# Solider.net
KiCad netlist of a schematic drawn in Altium Designer
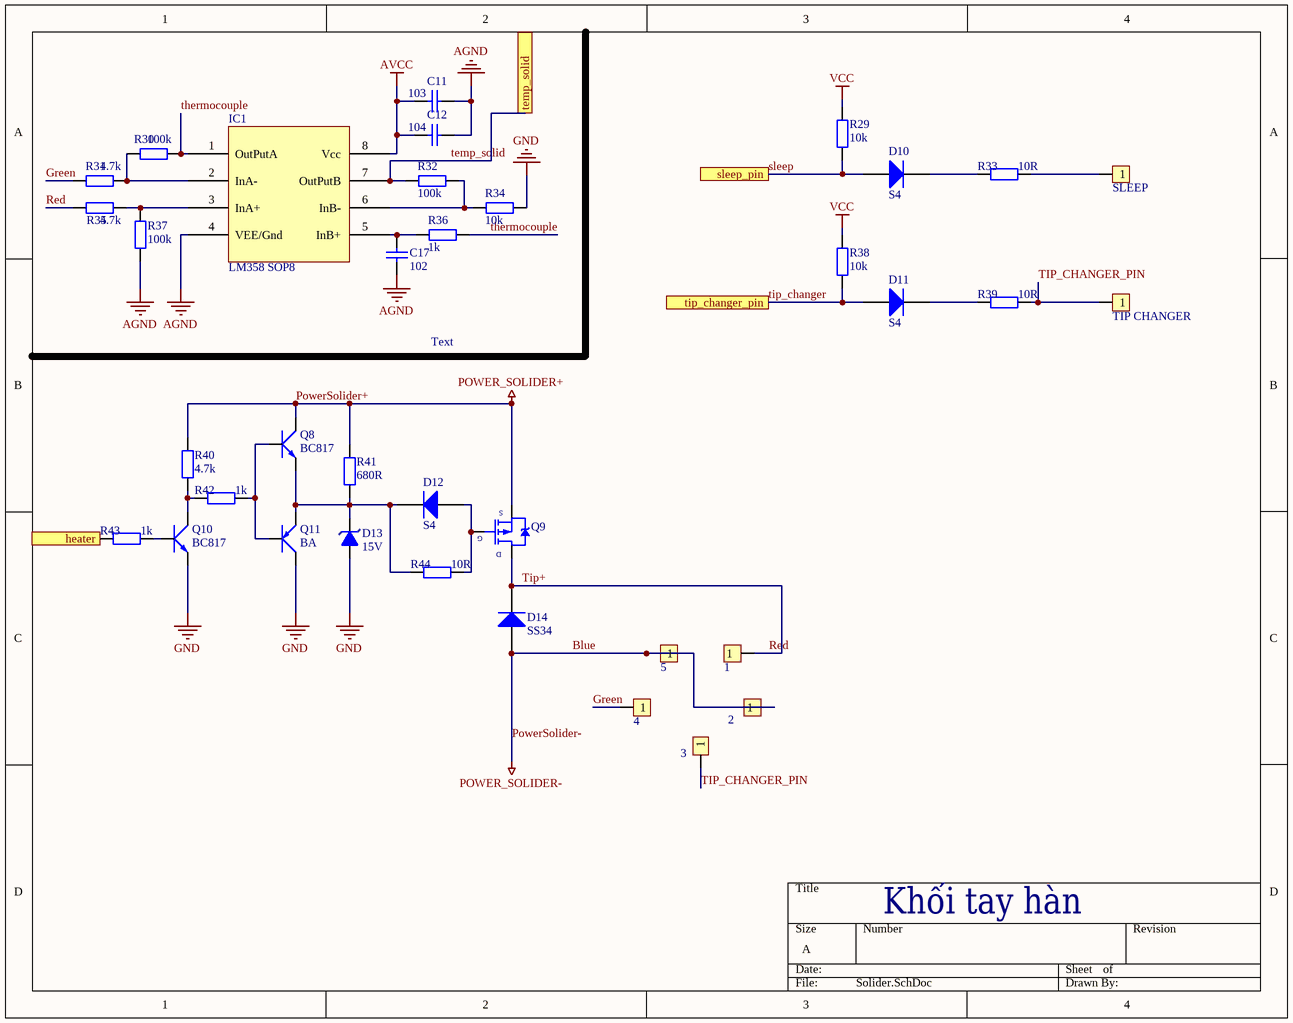
[diagram p0: Solider.SchDoc]

(export (version "E")
  (design (tool "Eeschema 10.0.6"))
  (components
    (comp (ref "C11")
      (value "103")
      (footprint "tu 0603")
      (description "Dán")
      (libsource (lib "Altium_Lib_by_KhueNguyenCreator") (part "Tu 0603 106 16V 20%"))
    )
    (comp (ref "C12")
      (value "104")
      (footprint "tu 0603")
      (description "Dán")
      (libsource (lib "Altium_Lib_by_KhueNguyenCreator") (part "Tu 0603 106 16V 20%"))
    )
    (comp (ref "C17")
      (value "102")
      (footprint "tu 0603")
      (description "Dán")
      (libsource (lib "Altium_Lib_by_KhueNguyenCreator") (part "Tu 0603 106 16V 20%"))
    )
    (comp (ref "D10")
      (value "S4")
      (footprint "DIODE SOD-123")
      (description "Dán")
      (libsource (lib "Driver4.0_Project_Fix_source_5V") (part "Diode S4"))
    )
    (comp (ref "D11")
      (value "S4")
      (footprint "DIODE SOD-123")
      (description "Dán")
      (libsource (lib "Driver4.0_Project_Fix_source_5V") (part "Diode S4"))
    )
    (comp (ref "D12")
      (value "S4")
      (footprint "DIODE SOD-123")
      (description "Dán")
      (libsource (lib "Altium_Lib_by_KhueNguyenCreator") (part "Diode S4"))
    )
    (comp (ref "D13")
      (value "15V")
      (footprint "DIODE ZENNER SMD SOD80")
      (description "Dán")
      (libsource (lib "Altium_Lib_by_KhueNguyenCreator") (part "Diode Zener 15V"))
    )
    (comp (ref "D14")
      (value "SS34")
      (footprint "DIODE SMA")
      (description "Dán")
      (libsource (lib "Altium_Lib_by_KhueNguyenCreator") (part "Diode SS34 ( 1N5822 )"))
    )
    (comp (ref "IC1")
      (value "LM358 SOP8")
      (footprint "SOP 8")
      (description "Dán")
      (libsource (lib "Altium_Lib_by_KhueNguyenCreator") (part "LM358 SOP8"))
    )
    (comp (ref "JP3")
      (value "SLEEP")
      (footprint "JP 1x1 DT")
      (description "Cắm")
      (libsource (lib "Altium_Lib_by_KhueNguyenCreator") (part "JP 1x1 2.54 Duc Cong"))
    )
    (comp (ref "JP4")
      (value "TIP CHANGER")
      (footprint "JP 1x1 DT")
      (description "Cắm")
      (libsource (lib "Altium_Lib_by_KhueNguyenCreator") (part "JP 1x1 2.54 Duc Cong"))
    )
    (comp (ref "JP5")
      (value "5")
      (footprint "JP 1x1 DT")
      (description "Cắm")
      (libsource (lib "Altium_Lib_by_KhueNguyenCreator") (part "JP 1x1 2.54 Duc Cong"))
    )
    (comp (ref "JP6")
      (value "1")
      (footprint "JP 1x1 DT")
      (description "Cắm")
      (libsource (lib "") (part "JP 1x1 2.54 Duc Cong_1"))
    )
    (comp (ref "JP7")
      (value "4")
      (footprint "JP 1x1 DT")
      (description "Cắm")
      (libsource (lib "Altium_Lib_by_KhueNguyenCreator") (part "JP 1x1 2.54 Duc Cong"))
    )
    (comp (ref "JP8")
      (value "2")
      (footprint "JP 1x1 DT")
      (description "Cắm")
      (libsource (lib "") (part "JP 1x1 2.54 Duc Cong_1"))
    )
    (comp (ref "JP9")
      (value "3")
      (footprint "JP 1x1 DT")
      (description "Cắm")
      (libsource (lib "") (part "JP 1x1 2.54 Duc Cong_2"))
    )
    (comp (ref "Q8")
      (value "BC817")
      (footprint "SOT-23")
      (description "SOT-23 - C8658")
      (libsource (lib "Altium_Lib_by_KhueNguyenCreator") (part "Trans BC817"))
    )
    (comp (ref "Q9")
      (value "IRF4905S")
      (footprint "D2PACK")
      (description "55V 75A")
      (libsource (lib "Driver4.0_Project_Fix_source_5V") (part "IRF4905S"))
    )
    (comp (ref "Q10")
      (value "BC817")
      (footprint "SOT-23")
      (description "SOT-23 - C8658")
      (libsource (lib "Altium_Lib_by_KhueNguyenCreator") (part "Trans BC817"))
    )
    (comp (ref "Q11")
      (value "BA")
      (footprint "SOT23")
      (description "PNP 600mW, ECB")
      (libsource (lib "Altium_Lib_by_KhueNguyenCreator") (part "Trans A1015 BA SMD"))
    )
    (comp (ref "R29")
      (value "10k")
      (footprint "Tro smd 0603")
      (description "Dán")
      (libsource (lib "Altium_Lib_by_KhueNguyenCreator") (part "Tro 0603 5% 10R"))
    )
    (comp (ref "R30")
      (value "100k")
      (footprint "Tro smd 0603")
      (description "Dán")
      (libsource (lib "Altium_Lib_by_KhueNguyenCreator") (part "Tro 0603 5% 10R"))
    )
    (comp (ref "R31")
      (value "4.7k")
      (footprint "Tro smd 0603")
      (description "Dán")
      (libsource (lib "Altium_Lib_by_KhueNguyenCreator") (part "Tro 0603 5% 10R"))
    )
    (comp (ref "R32")
      (value "100k")
      (footprint "Tro smd 0603")
      (description "Dán")
      (libsource (lib "Altium_Lib_by_KhueNguyenCreator") (part "Tro 0603 5% 10R"))
    )
    (comp (ref "R33")
      (value "10R")
      (footprint "Tro smd 0603")
      (description "Dán")
      (libsource (lib "Altium_Lib_by_KhueNguyenCreator") (part "Tro 0603 5% 10R"))
    )
    (comp (ref "R34")
      (value "10k")
      (footprint "Tro smd 0603")
      (description "Dán")
      (libsource (lib "Altium_Lib_by_KhueNguyenCreator") (part "Tro 0603 5% 10R"))
    )
    (comp (ref "R35")
      (value "4.7k")
      (footprint "Tro smd 0603")
      (description "Dán")
      (libsource (lib "Altium_Lib_by_KhueNguyenCreator") (part "Tro 0603 5% 10R"))
    )
    (comp (ref "R36")
      (value "1k")
      (footprint "Tro smd 0603")
      (description "Dán")
      (libsource (lib "Altium_Lib_by_KhueNguyenCreator") (part "Tro 0603 5% 10R"))
    )
    (comp (ref "R37")
      (value "100k")
      (footprint "Tro smd 0603")
      (description "Dán")
      (libsource (lib "Altium_Lib_by_KhueNguyenCreator") (part "Tro 0603 5% 10R"))
    )
    (comp (ref "R38")
      (value "10k")
      (footprint "Tro smd 0603")
      (description "Dán")
      (libsource (lib "Altium_Lib_by_KhueNguyenCreator") (part "Tro 0603 5% 10R"))
    )
    (comp (ref "R39")
      (value "10R")
      (footprint "Tro smd 0603")
      (description "Dán")
      (libsource (lib "Altium_Lib_by_KhueNguyenCreator") (part "Tro 0603 5% 10R"))
    )
    (comp (ref "R40")
      (value "4.7k")
      (footprint "Tro smd 0603")
      (description "Dán")
      (libsource (lib "Altium_Lib_by_KhueNguyenCreator") (part "Tro 0603 5% 10R"))
    )
    (comp (ref "R41")
      (value "680R")
      (footprint "tro vach 1/4w")
      (description "Cắm")
      (libsource (lib "Altium_Lib_by_KhueNguyenCreator") (part "Tro Vach 1/4W 5% 680R"))
    )
    (comp (ref "R42")
      (value "1k")
      (footprint "Tro smd 0603")
      (description "Dán")
      (libsource (lib "Altium_Lib_by_KhueNguyenCreator") (part "Tro 0603 5% 10R"))
    )
    (comp (ref "R43")
      (value "1k")
      (footprint "Tro smd 0603")
      (description "Dán")
      (libsource (lib "Altium_Lib_by_KhueNguyenCreator") (part "Tro 0603 5% 10R"))
    )
    (comp (ref "R44")
      (value "10R")
      (footprint "Tro smd 0603")
      (description "Dán")
      (libsource (lib "Altium_Lib_by_KhueNguyenCreator") (part "Tro 0603 5% 10R"))
    )
  )
  (nets
    (net (code "1") (name "/Green") (class "Default")
      (node (ref "JP7") (pin "1") (pinfunction "1_1") (pintype "passive"))
      (node (ref "R31") (pin "2") (pinfunction "2_2") (pintype "passive"))
    )
    (net (code "2") (name "/Red") (class "Default")
      (node (ref "D14") (pin "2") (pinfunction "K_2") (pintype "passive"))
      (node (ref "JP6") (pin "1") (pinfunction "1_1") (pintype "passive"))
      (node (ref "Q9") (pin "2") (pinfunction "D_2") (pintype "passive"))
      (node (ref "R35") (pin "2") (pinfunction "2_2") (pintype "passive"))
    )
    (net (code "3") (name "/TIP_CHANGER_PIN") (class "Default")
      (node (ref "JP4") (pin "1") (pinfunction "1_1") (pintype "passive"))
      (node (ref "JP9") (pin "1") (pinfunction "1_1") (pintype "passive"))
      (node (ref "R39") (pin "2") (pinfunction "2_2") (pintype "passive"))
    )
    (net (code "4") (name "/heater") (class "Default")
      (node (ref "R43") (pin "1") (pinfunction "1_1") (pintype "passive"))
    )
    (net (code "5") (name "/sleep") (class "Default")
      (node (ref "D10") (pin "1") (pinfunction "A_1") (pintype "passive"))
      (node (ref "R29") (pin "1") (pinfunction "1_1") (pintype "passive"))
    )
    (net (code "6") (name "/temp_solid") (class "Default")
      (node (ref "IC1") (pin "7") (pinfunction "OutPutB_7") (pintype "passive"))
      (node (ref "R32") (pin "1") (pinfunction "1_1") (pintype "passive"))
    )
    (net (code "7") (name "/thermocouple") (class "Default")
      (node (ref "IC1") (pin "1") (pinfunction "OutPutA_1") (pintype "passive"))
      (node (ref "R30") (pin "2") (pinfunction "2_2") (pintype "passive"))
      (node (ref "R36") (pin "1") (pinfunction "1_1") (pintype "passive"))
    )
    (net (code "8") (name "/tip_changer") (class "Default")
      (node (ref "D11") (pin "1") (pinfunction "A_1") (pintype "passive"))
      (node (ref "R38") (pin "1") (pinfunction "1_1") (pintype "passive"))
    )
    (net (code "9") (name "AGND") (class "Default")
      (node (ref "C11") (pin "2") (pinfunction "2_2") (pintype "passive"))
      (node (ref "C12") (pin "2") (pinfunction "2_2") (pintype "passive"))
      (node (ref "C17") (pin "1") (pinfunction "1_1") (pintype "passive"))
      (node (ref "IC1") (pin "4") (pinfunction "VEE/Gnd_4") (pintype "passive"))
      (node (ref "R37") (pin "2") (pinfunction "2_2") (pintype "passive"))
    )
    (net (code "10") (name "AVCC") (class "Default")
      (node (ref "C11") (pin "1") (pinfunction "1_1") (pintype "passive"))
      (node (ref "C12") (pin "1") (pinfunction "1_1") (pintype "passive"))
      (node (ref "IC1") (pin "8") (pinfunction "Vcc_8") (pintype "passive"))
    )
    (net (code "11") (name "GND") (class "Default")
      (node (ref "D13") (pin "1") (pinfunction "A_1") (pintype "passive"))
      (node (ref "Q10") (pin "2") (pinfunction "E_2") (pintype "passive"))
      (node (ref "Q11") (pin "3") (pinfunction "C_3") (pintype "passive"))
      (node (ref "R34") (pin "2") (pinfunction "2_2") (pintype "passive"))
    )
    (net (code "12") (name "Net-(D10-K)") (class "Default")
      (node (ref "D10") (pin "2") (pinfunction "K_2") (pintype "passive"))
      (node (ref "R33") (pin "1") (pinfunction "1_1") (pintype "passive"))
    )
    (net (code "13") (name "Net-(D11-K)") (class "Default")
      (node (ref "D11") (pin "2") (pinfunction "K_2") (pintype "passive"))
      (node (ref "R39") (pin "1") (pinfunction "1_1") (pintype "passive"))
    )
    (net (code "14") (name "Net-(D12-A)") (class "Default")
      (node (ref "D12") (pin "1") (pinfunction "A_1") (pintype "passive"))
      (node (ref "Q9") (pin "1") (pinfunction "G_1") (pintype "passive"))
      (node (ref "R44") (pin "2") (pinfunction "2_2") (pintype "passive"))
    )
    (net (code "15") (name "Net-(D12-K)") (class "Default")
      (node (ref "D12") (pin "2") (pinfunction "K_2") (pintype "passive"))
      (node (ref "D13") (pin "2") (pinfunction "K_2") (pintype "passive"))
      (node (ref "Q11") (pin "2") (pinfunction "E_2") (pintype "passive"))
      (node (ref "Q8") (pin "2") (pinfunction "E_2") (pintype "passive"))
      (node (ref "R41") (pin "1") (pinfunction "1_1") (pintype "passive"))
      (node (ref "R44") (pin "1") (pinfunction "1_1") (pintype "passive"))
    )
    (net (code "16") (name "Net-(IC1-InA+)") (class "Default")
      (node (ref "IC1") (pin "3") (pinfunction "InA+_3") (pintype "passive"))
      (node (ref "R35") (pin "1") (pinfunction "1_1") (pintype "passive"))
      (node (ref "R37") (pin "1") (pinfunction "1_1") (pintype "passive"))
    )
    (net (code "17") (name "Net-(IC1-InA-)") (class "Default")
      (node (ref "IC1") (pin "2") (pinfunction "InA-_2") (pintype "passive"))
      (node (ref "R30") (pin "1") (pinfunction "1_1") (pintype "passive"))
      (node (ref "R31") (pin "1") (pinfunction "1_1") (pintype "passive"))
    )
    (net (code "18") (name "Net-(IC1-InB+)") (class "Default")
      (node (ref "C17") (pin "2") (pinfunction "2_2") (pintype "passive"))
      (node (ref "IC1") (pin "5") (pinfunction "InB+_5") (pintype "passive"))
      (node (ref "R36") (pin "2") (pinfunction "2_2") (pintype "passive"))
    )
    (net (code "19") (name "Net-(IC1-InB-)") (class "Default")
      (node (ref "IC1") (pin "6") (pinfunction "InB-_6") (pintype "passive"))
      (node (ref "R32") (pin "2") (pinfunction "2_2") (pintype "passive"))
      (node (ref "R34") (pin "1") (pinfunction "1_1") (pintype "passive"))
    )
    (net (code "20") (name "Net-(JP3-Pad1)") (class "Default")
      (node (ref "JP3") (pin "1") (pinfunction "1_1") (pintype "passive"))
      (node (ref "R33") (pin "2") (pinfunction "2_2") (pintype "passive"))
    )
    (net (code "21") (name "Net-(Q10-B)") (class "Default")
      (node (ref "Q10") (pin "1") (pinfunction "B_1") (pintype "passive"))
      (node (ref "R43") (pin "2") (pinfunction "2_2") (pintype "passive"))
    )
    (net (code "22") (name "Net-(Q10-C)") (class "Default")
      (node (ref "Q10") (pin "3") (pinfunction "C_3") (pintype "passive"))
      (node (ref "R40") (pin "1") (pinfunction "1_1") (pintype "passive"))
      (node (ref "R42") (pin "1") (pinfunction "1_1") (pintype "passive"))
    )
    (net (code "23") (name "Net-(Q11-B)") (class "Default")
      (node (ref "Q11") (pin "1") (pinfunction "B_1") (pintype "passive"))
      (node (ref "Q8") (pin "1") (pinfunction "B_1") (pintype "passive"))
      (node (ref "R42") (pin "2") (pinfunction "2_2") (pintype "passive"))
    )
    (net (code "24") (name "POWER_SOLIDER+") (class "Default")
      (node (ref "Q8") (pin "3") (pinfunction "C_3") (pintype "passive"))
      (node (ref "Q9") (pin "3") (pinfunction "S_3") (pintype "passive"))
      (node (ref "R40") (pin "2") (pinfunction "2_2") (pintype "passive"))
      (node (ref "R41") (pin "2") (pinfunction "2_2") (pintype "passive"))
    )
    (net (code "25") (name "POWER_SOLIDER-") (class "Default")
      (node (ref "D14") (pin "1") (pinfunction "A_1") (pintype "passive"))
      (node (ref "JP5") (pin "1") (pinfunction "1_1") (pintype "passive"))
      (node (ref "JP8") (pin "1") (pinfunction "1_1") (pintype "passive"))
    )
    (net (code "26") (name "VCC") (class "Default")
      (node (ref "R29") (pin "2") (pinfunction "2_2") (pintype "passive"))
      (node (ref "R38") (pin "2") (pinfunction "2_2") (pintype "passive"))
    )
  )
)
